# stmboard.net
KiCad netlist of a schematic drawn in EAGLE
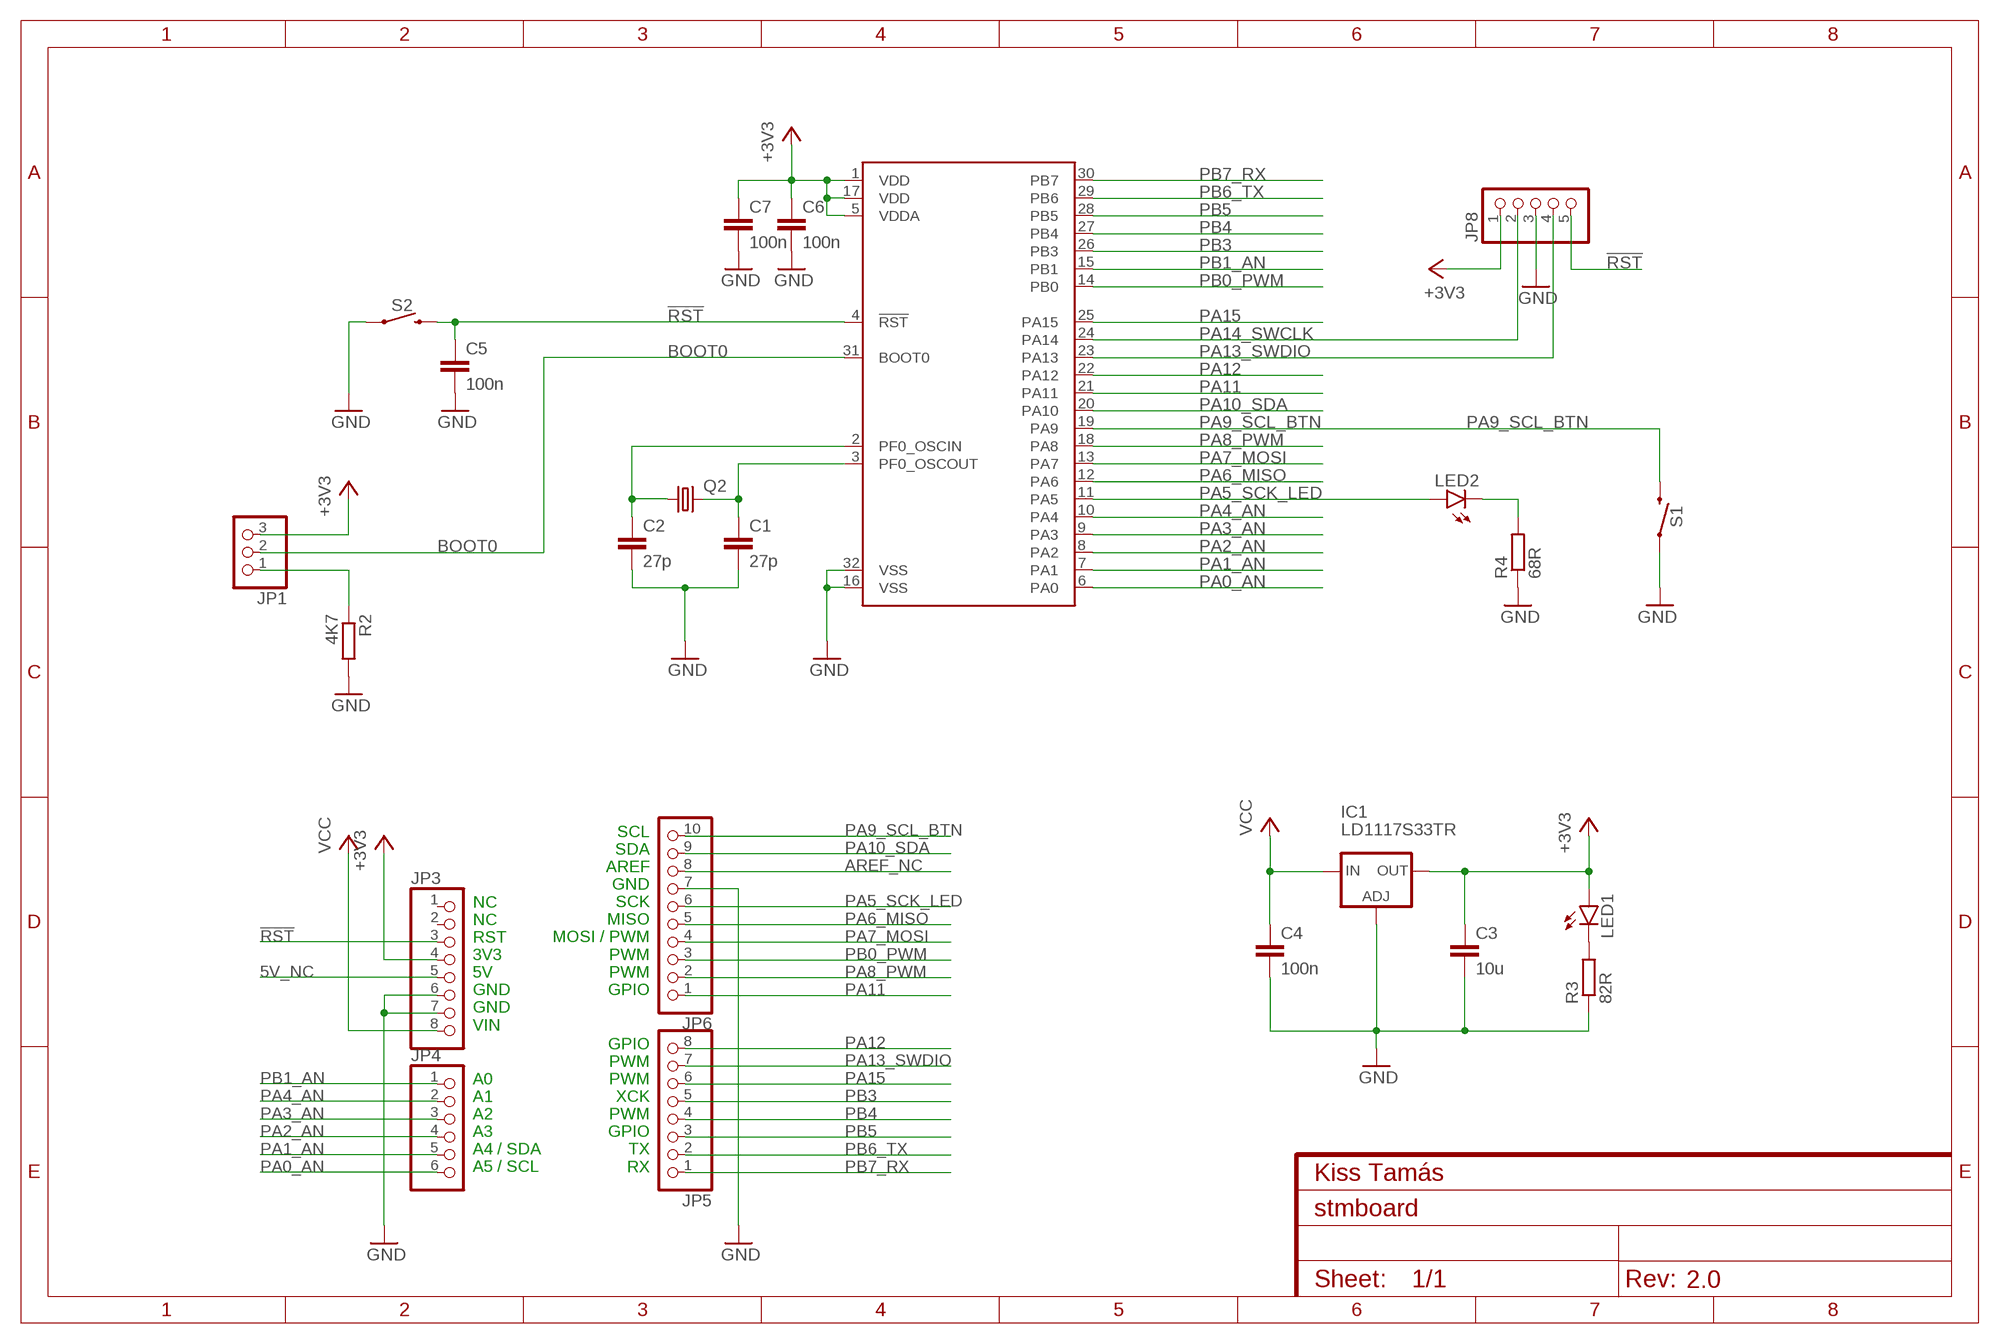
[diagram p0: schematic, sheet 1]

(export (version "E")
  (design (tool "Eeschema 10.0.6"))
  (components
    (comp (ref "C1")
      (value "27p")
      (footprint "eagle-import:C1206")
      (libsource (lib "eagle-import") (part "C-EUC1206"))
    )
    (comp (ref "C2")
      (value "27p")
      (footprint "eagle-import:C1206")
      (libsource (lib "eagle-import") (part "C-EUC1206"))
    )
    (comp (ref "C3")
      (value "10u")
      (footprint "eagle-import:C1206K")
      (libsource (lib "eagle-import") (part "C-EUC1206K"))
    )
    (comp (ref "C4")
      (value "100n")
      (footprint "eagle-import:C1206K")
      (libsource (lib "eagle-import") (part "C-EUC1206K"))
    )
    (comp (ref "C5")
      (value "100n")
      (footprint "eagle-import:C1206K")
      (libsource (lib "eagle-import") (part "C-EUC1206K"))
    )
    (comp (ref "C6")
      (value "100n")
      (footprint "eagle-import:C1206K")
      (libsource (lib "eagle-import") (part "C-EUC1206K"))
    )
    (comp (ref "C7")
      (value "100n")
      (footprint "eagle-import:C1206K")
      (libsource (lib "eagle-import") (part "C-EUC1206K"))
    )
    (comp (ref "IC1")
      (value "LD1117S33TR")
      (footprint "eagle-import:SOT223")
      (libsource (lib "eagle-import") (part "LD117A?S12TR"))
    )
    (comp (ref "JP1")
      (value "PINHD-1X3")
      (footprint "eagle-import:1X03")
      (libsource (lib "eagle-import") (part "PINHD-1X3"))
    )
    (comp (ref "JP3")
      (value "PINHD-1X8")
      (footprint "eagle-import:1X08")
      (libsource (lib "eagle-import") (part "PINHD-1X8"))
    )
    (comp (ref "JP4")
      (value "PINHD-1X6")
      (footprint "eagle-import:1X06")
      (libsource (lib "eagle-import") (part "PINHD-1X6"))
    )
    (comp (ref "JP5")
      (value "PINHD-1X8")
      (footprint "eagle-import:1X08")
      (libsource (lib "eagle-import") (part "PINHD-1X8"))
    )
    (comp (ref "JP6")
      (value "PINHD-1X10")
      (footprint "eagle-import:1X10")
      (libsource (lib "eagle-import") (part "PINHD-1X10"))
    )
    (comp (ref "JP8")
      (value "PINHD-1X5")
      (footprint "eagle-import:1X05")
      (libsource (lib "eagle-import") (part "PINHD-1X5"))
    )
    (comp (ref "LED1")
      (value "LEDSMT1206")
      (footprint "eagle-import:1206")
      (libsource (lib "eagle-import") (part "LEDSMT1206"))
    )
    (comp (ref "LED2")
      (value "LEDSMT1206")
      (footprint "eagle-import:1206")
      (libsource (lib "eagle-import") (part "LEDSMT1206"))
    )
    (comp (ref "Q2")
      (value "CRYSTALSM49")
      (footprint "eagle-import:SM49")
      (libsource (lib "eagle-import") (part "CRYSTALSM49"))
    )
    (comp (ref "R2")
      (value "4K7")
      (footprint "eagle-import:M1206")
      (libsource (lib "eagle-import") (part "R-EU_M1206"))
    )
    (comp (ref "R3")
      (value "82R")
      (footprint "eagle-import:M1206")
      (libsource (lib "eagle-import") (part "R-EU_M1206"))
    )
    (comp (ref "R4")
      (value "68R")
      (footprint "eagle-import:M1206")
      (libsource (lib "eagle-import") (part "R-EU_M1206"))
    )
    (comp (ref "S1")
      (value "MOMENTARY-SWITCH-SPST-SMD-6.0X3.5MM")
      (footprint "eagle-import:TACTILE_SWITCH_SMD_6.0X3.5MM")
      (libsource (lib "eagle-import") (part "MOMENTARY-SWITCH-SPST-SMD-6.0X3.5MM"))
    )
    (comp (ref "S2")
      (value "MOMENTARY-SWITCH-SPST-SMD-6.0X3.5MM")
      (footprint "eagle-import:TACTILE_SWITCH_SMD_6.0X3.5MM")
      (libsource (lib "eagle-import") (part "MOMENTARY-SWITCH-SPST-SMD-6.0X3.5MM"))
    )
    (comp (ref "U$1")
      (value "STM32F030")
      (footprint "eagle-import:TQFP32-08")
      (libsource (lib "eagle-import") (part "STM32F030"))
    )
  )
  (nets
    (net (code "1") (name "+3V3") (class "Default")
      (node (ref "C3") (pin "1") (pinfunction "1_1") (pintype "passive"))
      (node (ref "C6") (pin "1") (pinfunction "1_1") (pintype "passive"))
      (node (ref "C7") (pin "1") (pinfunction "1_1") (pintype "passive"))
      (node (ref "IC1") (pin "4") (pinfunction "OUT_4") (pintype "passive"))
      (node (ref "JP1") (pin "3") (pinfunction "3_3") (pintype "passive"))
      (node (ref "JP3") (pin "4") (pinfunction "4_4") (pintype "passive"))
      (node (ref "JP8") (pin "1") (pinfunction "1_1") (pintype "passive"))
      (node (ref "LED1") (pin "A") (pinfunction "A_A") (pintype "passive"))
      (node (ref "U$1") (pin "1") (pinfunction "VDD_1") (pintype "bidirectional"))
      (node (ref "U$1") (pin "17") (pinfunction "VDD_17") (pintype "bidirectional"))
      (node (ref "U$1") (pin "5") (pinfunction "VDDA_5") (pintype "bidirectional"))
    )
    (net (code "2") (name "/5V_NC") (class "Default")
      (node (ref "JP3") (pin "5") (pinfunction "5_5") (pintype "passive"))
    )
    (net (code "3") (name "/AREF_NC") (class "Default")
      (node (ref "JP6") (pin "8") (pinfunction "8_8") (pintype "passive"))
    )
    (net (code "4") (name "/BOOT0") (class "Default")
      (node (ref "JP1") (pin "2") (pinfunction "2_2") (pintype "passive"))
      (node (ref "U$1") (pin "31") (pinfunction "BOOT0_31") (pintype "bidirectional"))
    )
    (net (code "5") (name "/PA0_AN") (class "Default")
      (node (ref "JP4") (pin "6") (pinfunction "6_6") (pintype "passive"))
      (node (ref "U$1") (pin "6") (pinfunction "PA0_6") (pintype "bidirectional"))
    )
    (net (code "6") (name "/PA1_AN") (class "Default")
      (node (ref "JP4") (pin "5") (pinfunction "5_5") (pintype "passive"))
      (node (ref "U$1") (pin "7") (pinfunction "PA1_7") (pintype "bidirectional"))
    )
    (net (code "7") (name "/PA2_AN") (class "Default")
      (node (ref "JP4") (pin "4") (pinfunction "4_4") (pintype "passive"))
      (node (ref "U$1") (pin "8") (pinfunction "PA2_8") (pintype "bidirectional"))
    )
    (net (code "8") (name "/PA3_AN") (class "Default")
      (node (ref "JP4") (pin "3") (pinfunction "3_3") (pintype "passive"))
      (node (ref "U$1") (pin "9") (pinfunction "PA3_9") (pintype "bidirectional"))
    )
    (net (code "9") (name "/PA4_AN") (class "Default")
      (node (ref "JP4") (pin "2") (pinfunction "2_2") (pintype "passive"))
      (node (ref "U$1") (pin "10") (pinfunction "PA4_10") (pintype "bidirectional"))
    )
    (net (code "10") (name "/PA5_SCK_LED") (class "Default")
      (node (ref "JP6") (pin "6") (pinfunction "6_6") (pintype "passive"))
      (node (ref "LED2") (pin "A") (pinfunction "A_A") (pintype "passive"))
      (node (ref "U$1") (pin "11") (pinfunction "PA5_11") (pintype "bidirectional"))
    )
    (net (code "11") (name "/PA6_MISO") (class "Default")
      (node (ref "JP6") (pin "5") (pinfunction "5_5") (pintype "passive"))
      (node (ref "U$1") (pin "12") (pinfunction "PA6_12") (pintype "bidirectional"))
    )
    (net (code "12") (name "/PA7_MOSI") (class "Default")
      (node (ref "JP6") (pin "4") (pinfunction "4_4") (pintype "passive"))
      (node (ref "U$1") (pin "13") (pinfunction "PA7_13") (pintype "bidirectional"))
    )
    (net (code "13") (name "/PA8_PWM") (class "Default")
      (node (ref "JP6") (pin "2") (pinfunction "2_2") (pintype "passive"))
      (node (ref "U$1") (pin "18") (pinfunction "PA8_18") (pintype "bidirectional"))
    )
    (net (code "14") (name "/PA9_SCL_BTN") (class "Default")
      (node (ref "JP6") (pin "10") (pinfunction "10_10") (pintype "passive"))
      (node (ref "S1") (pin "2") (pinfunction "2_2") (pintype "passive"))
      (node (ref "U$1") (pin "19") (pinfunction "PA9_19") (pintype "bidirectional"))
    )
    (net (code "15") (name "/PA10_SDA") (class "Default")
      (node (ref "JP6") (pin "9") (pinfunction "9_9") (pintype "passive"))
      (node (ref "U$1") (pin "20") (pinfunction "PA10_20") (pintype "bidirectional"))
    )
    (net (code "16") (name "/PA11") (class "Default")
      (node (ref "JP6") (pin "1") (pinfunction "1_1") (pintype "passive"))
      (node (ref "U$1") (pin "21") (pinfunction "PA11_21") (pintype "bidirectional"))
    )
    (net (code "17") (name "/PA12") (class "Default")
      (node (ref "JP5") (pin "8") (pinfunction "8_8") (pintype "passive"))
      (node (ref "U$1") (pin "22") (pinfunction "PA12_22") (pintype "bidirectional"))
    )
    (net (code "18") (name "/PA13_SWDIO") (class "Default")
      (node (ref "JP5") (pin "7") (pinfunction "7_7") (pintype "passive"))
      (node (ref "JP8") (pin "4") (pinfunction "4_4") (pintype "passive"))
      (node (ref "U$1") (pin "23") (pinfunction "PA13_23") (pintype "bidirectional"))
    )
    (net (code "19") (name "/PA14_SWCLK") (class "Default")
      (node (ref "JP8") (pin "2") (pinfunction "2_2") (pintype "passive"))
      (node (ref "U$1") (pin "24") (pinfunction "PA14_24") (pintype "bidirectional"))
    )
    (net (code "20") (name "/PA15") (class "Default")
      (node (ref "JP5") (pin "6") (pinfunction "6_6") (pintype "passive"))
      (node (ref "U$1") (pin "25") (pinfunction "PA15_25") (pintype "bidirectional"))
    )
    (net (code "21") (name "/PB0_PWM") (class "Default")
      (node (ref "JP6") (pin "3") (pinfunction "3_3") (pintype "passive"))
      (node (ref "U$1") (pin "14") (pinfunction "PB0_14") (pintype "bidirectional"))
    )
    (net (code "22") (name "/PB1_AN") (class "Default")
      (node (ref "JP4") (pin "1") (pinfunction "1_1") (pintype "passive"))
      (node (ref "U$1") (pin "15") (pinfunction "PB1_15") (pintype "bidirectional"))
    )
    (net (code "23") (name "/PB3") (class "Default")
      (node (ref "JP5") (pin "5") (pinfunction "5_5") (pintype "passive"))
      (node (ref "U$1") (pin "26") (pinfunction "PB3_26") (pintype "bidirectional"))
    )
    (net (code "24") (name "/PB4") (class "Default")
      (node (ref "JP5") (pin "4") (pinfunction "4_4") (pintype "passive"))
      (node (ref "U$1") (pin "27") (pinfunction "PB4_27") (pintype "bidirectional"))
    )
    (net (code "25") (name "/PB5") (class "Default")
      (node (ref "JP5") (pin "3") (pinfunction "3_3") (pintype "passive"))
      (node (ref "U$1") (pin "28") (pinfunction "PB5_28") (pintype "bidirectional"))
    )
    (net (code "26") (name "/PB6_TX") (class "Default")
      (node (ref "JP5") (pin "2") (pinfunction "2_2") (pintype "passive"))
      (node (ref "U$1") (pin "29") (pinfunction "PB6_29") (pintype "bidirectional"))
    )
    (net (code "27") (name "/PB7_RX") (class "Default")
      (node (ref "JP5") (pin "1") (pinfunction "1_1") (pintype "passive"))
      (node (ref "U$1") (pin "30") (pinfunction "PB7_30") (pintype "bidirectional"))
    )
    (net (code "28") (name "/~{RST}") (class "Default")
      (node (ref "C5") (pin "1") (pinfunction "1_1") (pintype "passive"))
      (node (ref "JP3") (pin "3") (pinfunction "3_3") (pintype "passive"))
      (node (ref "JP8") (pin "5") (pinfunction "5_5") (pintype "passive"))
      (node (ref "S2") (pin "2") (pinfunction "2_2") (pintype "passive"))
      (node (ref "U$1") (pin "4") (pinfunction "~{RST}_4") (pintype "bidirectional"))
    )
    (net (code "29") (name "GND") (class "Default")
      (node (ref "C1") (pin "2") (pinfunction "2_2") (pintype "passive"))
      (node (ref "C2") (pin "2") (pinfunction "2_2") (pintype "passive"))
      (node (ref "C3") (pin "2") (pinfunction "2_2") (pintype "passive"))
      (node (ref "C4") (pin "2") (pinfunction "2_2") (pintype "passive"))
      (node (ref "C5") (pin "2") (pinfunction "2_2") (pintype "passive"))
      (node (ref "C6") (pin "2") (pinfunction "2_2") (pintype "passive"))
      (node (ref "C7") (pin "2") (pinfunction "2_2") (pintype "passive"))
      (node (ref "IC1") (pin "1") (pinfunction "ADJ_1") (pintype "input"))
      (node (ref "JP3") (pin "6") (pinfunction "6_6") (pintype "passive"))
      (node (ref "JP3") (pin "7") (pinfunction "7_7") (pintype "passive"))
      (node (ref "JP6") (pin "7") (pinfunction "7_7") (pintype "passive"))
      (node (ref "JP8") (pin "3") (pinfunction "3_3") (pintype "passive"))
      (node (ref "R2") (pin "2") (pinfunction "2_2") (pintype "passive"))
      (node (ref "R3") (pin "1") (pinfunction "1_1") (pintype "passive"))
      (node (ref "R4") (pin "1") (pinfunction "1_1") (pintype "passive"))
      (node (ref "S1") (pin "1") (pinfunction "1_1") (pintype "passive"))
      (node (ref "S2") (pin "1") (pinfunction "1_1") (pintype "passive"))
      (node (ref "U$1") (pin "16") (pinfunction "VSS_16") (pintype "bidirectional"))
      (node (ref "U$1") (pin "32") (pinfunction "VSS_32") (pintype "bidirectional"))
    )
    (net (code "30") (name "Net-(JP1-Pad1)") (class "Default")
      (node (ref "JP1") (pin "1") (pinfunction "1_1") (pintype "passive"))
      (node (ref "R2") (pin "1") (pinfunction "1_1") (pintype "passive"))
    )
    (net (code "31") (name "Net-(LED1-PadC)") (class "Default")
      (node (ref "LED1") (pin "C") (pinfunction "C_C") (pintype "passive"))
      (node (ref "R3") (pin "2") (pinfunction "2_2") (pintype "passive"))
    )
    (net (code "32") (name "Net-(LED2-PadC)") (class "Default")
      (node (ref "LED2") (pin "C") (pinfunction "C_C") (pintype "passive"))
      (node (ref "R4") (pin "2") (pinfunction "2_2") (pintype "passive"))
    )
    (net (code "33") (name "Net-(U$1-PF0_OSCIN)") (class "Default")
      (node (ref "C2") (pin "1") (pinfunction "1_1") (pintype "passive"))
      (node (ref "Q2") (pin "1") (pinfunction "1_1") (pintype "passive"))
      (node (ref "U$1") (pin "2") (pinfunction "PF0_OSCIN_2") (pintype "bidirectional"))
    )
    (net (code "34") (name "Net-(U$1-PF0_OSCOUT)") (class "Default")
      (node (ref "C1") (pin "1") (pinfunction "1_1") (pintype "passive"))
      (node (ref "Q2") (pin "2") (pinfunction "2_2") (pintype "passive"))
      (node (ref "U$1") (pin "3") (pinfunction "PF0_OSCOUT_3") (pintype "bidirectional"))
    )
    (net (code "35") (name "VCC") (class "Default")
      (node (ref "C4") (pin "1") (pinfunction "1_1") (pintype "passive"))
      (node (ref "IC1") (pin "3") (pinfunction "IN_3") (pintype "input"))
      (node (ref "JP3") (pin "8") (pinfunction "8_8") (pintype "passive"))
    )
    (net (code "36") (name "unconnected-(JP3-Pad1)") (class "Default")
      (node (ref "JP3") (pin "1") (pinfunction "1_1") (pintype "passive"))
    )
    (net (code "37") (name "unconnected-(JP3-Pad2)") (class "Default")
      (node (ref "JP3") (pin "2") (pinfunction "2_2") (pintype "passive"))
    )
  )
)
